# LED_Orange_Direct.net
KiCad netlist of a schematic drawn in Altium Designer
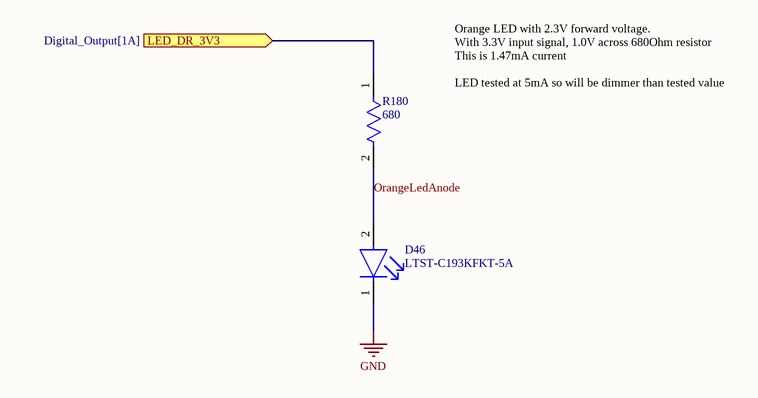
[diagram p0:  LED_Orange_Direct.SchDoc]

(export (version "E")
  (design (tool "Eeschema 10.0.6"))
  (components
    (comp (ref "D46")
      (value "LTST-C193KFKT-5A")
      (footprint "FP-LTST-C193KGKT-5A-MFG")
      (description "LED orange LED0603 wavelength 605nm light intensity 11~45mcd vertical sticker")
      (libsource (lib "HIL RIG FYP") (part "8706943c75ba83719d021d2fdc84c58"))
    )
    (comp (ref "R180")
      (value "680")
      (footprint "FP-CRCW0603-e3-IPC_C")
      (description "Fixed Resistor, Metal Glaze/Thick Film, 0.1W, 680ohm, 75V, 5% +/-Tol, Surface Mount, 0603")
      (fields (field (name "TOLERANCE") "5%") (field (name "Comment") "CRCW0603680RJNEA"))
      (libsource (lib "HIL RIG FYP") (part "1029c3af85768c4190bb7ad29bc67b5"))
    )
  )
  (nets
    (net (code "1") (name "/LED_DR_3V3") (class "Default")
      (node (ref "R180") (pin "1") (pinfunction "1_1") (pintype "passive"))
    )
    (net (code "2") (name "/OrangeLedAnode") (class "Default")
      (node (ref "D46") (pin "2") (pinfunction "A_2") (pintype "passive"))
      (node (ref "R180") (pin "2") (pinfunction "2_2") (pintype "passive"))
    )
    (net (code "3") (name "GND") (class "Default")
      (node (ref "D46") (pin "1") (pinfunction "C_1") (pintype "passive"))
    )
  )
)
